# BATT_DISP.net
KiCad netlist of a schematic drawn in EAGLE
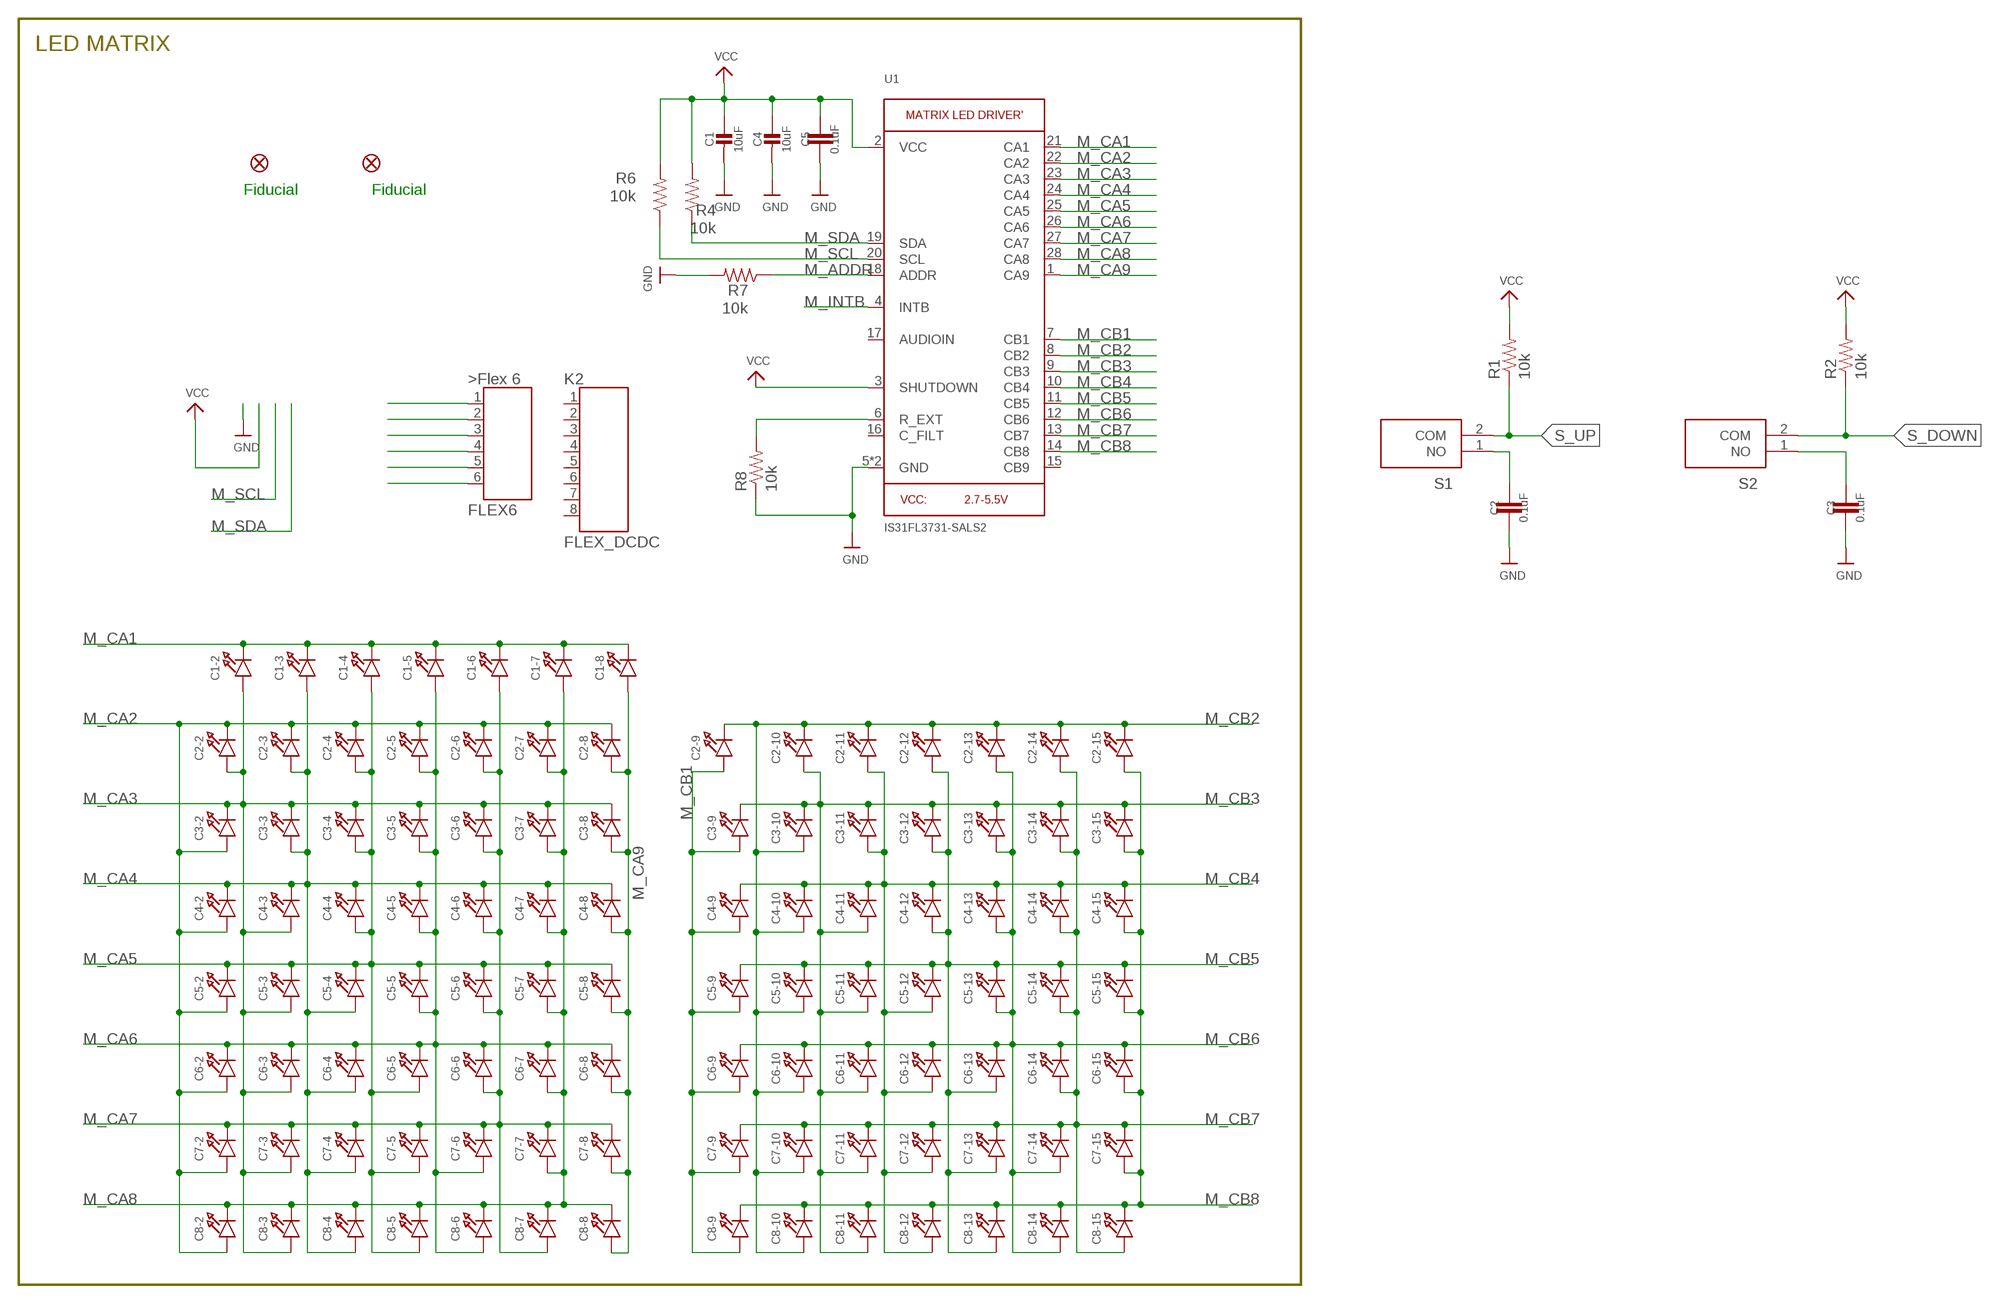
[diagram p0: schematic, sheet 1]

(export (version "E")
  (design (tool "Eeschema 10.0.6"))
  (components
    (comp (ref "C1")
      (value "10uF")
      (footprint "eagle-import:0805-NO")
      (libsource (lib "eagle-import") (part "CAP_CERAMIC0805-NOOUTLINE"))
    )
    (comp (ref "C1-2")
      (value "LED0402_NOOUTLINE")
      (footprint "eagle-import:CHIPLED_0402_NOOUTLINE")
      (libsource (lib "eagle-import") (part "LED0402_NOOUTLINE"))
    )
    (comp (ref "C1-3")
      (value "LED0402_NOOUTLINE")
      (footprint "eagle-import:CHIPLED_0402_NOOUTLINE")
      (libsource (lib "eagle-import") (part "LED0402_NOOUTLINE"))
    )
    (comp (ref "C1-4")
      (value "LED0402_NOOUTLINE")
      (footprint "eagle-import:CHIPLED_0402_NOOUTLINE")
      (libsource (lib "eagle-import") (part "LED0402_NOOUTLINE"))
    )
    (comp (ref "C1-5")
      (value "LED0402_NOOUTLINE")
      (footprint "eagle-import:CHIPLED_0402_NOOUTLINE")
      (libsource (lib "eagle-import") (part "LED0402_NOOUTLINE"))
    )
    (comp (ref "C1-6")
      (value "LED0402_NOOUTLINE")
      (footprint "eagle-import:CHIPLED_0402_NOOUTLINE")
      (libsource (lib "eagle-import") (part "LED0402_NOOUTLINE"))
    )
    (comp (ref "C1-7")
      (value "LED0402_NOOUTLINE")
      (footprint "eagle-import:CHIPLED_0402_NOOUTLINE")
      (libsource (lib "eagle-import") (part "LED0402_NOOUTLINE"))
    )
    (comp (ref "C1-8")
      (value "LED0402_NOOUTLINE")
      (footprint "eagle-import:CHIPLED_0402_NOOUTLINE")
      (libsource (lib "eagle-import") (part "LED0402_NOOUTLINE"))
    )
    (comp (ref "C2")
      (value "0.1uF")
      (footprint "eagle-import:0603")
      (libsource (lib "eagle-import") (part "0.1UF-0603-25V-5%"))
    )
    (comp (ref "C2-2")
      (value "LED0402_NOOUTLINE")
      (footprint "eagle-import:CHIPLED_0402_NOOUTLINE")
      (libsource (lib "eagle-import") (part "LED0402_NOOUTLINE"))
    )
    (comp (ref "C2-3")
      (value "LED0402_NOOUTLINE")
      (footprint "eagle-import:CHIPLED_0402_NOOUTLINE")
      (libsource (lib "eagle-import") (part "LED0402_NOOUTLINE"))
    )
    (comp (ref "C2-4")
      (value "LED0402_NOOUTLINE")
      (footprint "eagle-import:CHIPLED_0402_NOOUTLINE")
      (libsource (lib "eagle-import") (part "LED0402_NOOUTLINE"))
    )
    (comp (ref "C2-5")
      (value "LED0402_NOOUTLINE")
      (footprint "eagle-import:CHIPLED_0402_NOOUTLINE")
      (libsource (lib "eagle-import") (part "LED0402_NOOUTLINE"))
    )
    (comp (ref "C2-6")
      (value "LED0402_NOOUTLINE")
      (footprint "eagle-import:CHIPLED_0402_NOOUTLINE")
      (libsource (lib "eagle-import") (part "LED0402_NOOUTLINE"))
    )
    (comp (ref "C2-7")
      (value "LED0402_NOOUTLINE")
      (footprint "eagle-import:CHIPLED_0402_NOOUTLINE")
      (libsource (lib "eagle-import") (part "LED0402_NOOUTLINE"))
    )
    (comp (ref "C2-8")
      (value "LED0402_NOOUTLINE")
      (footprint "eagle-import:CHIPLED_0402_NOOUTLINE")
      (libsource (lib "eagle-import") (part "LED0402_NOOUTLINE"))
    )
    (comp (ref "C2-9")
      (value "LED0402_NOOUTLINE")
      (footprint "eagle-import:CHIPLED_0402_NOOUTLINE")
      (libsource (lib "eagle-import") (part "LED0402_NOOUTLINE"))
    )
    (comp (ref "C2-10")
      (value "LED0402_NOOUTLINE")
      (footprint "eagle-import:CHIPLED_0402_NOOUTLINE")
      (libsource (lib "eagle-import") (part "LED0402_NOOUTLINE"))
    )
    (comp (ref "C2-11")
      (value "LED0402_NOOUTLINE")
      (footprint "eagle-import:CHIPLED_0402_NOOUTLINE")
      (libsource (lib "eagle-import") (part "LED0402_NOOUTLINE"))
    )
    (comp (ref "C2-12")
      (value "LED0402_NOOUTLINE")
      (footprint "eagle-import:CHIPLED_0402_NOOUTLINE")
      (libsource (lib "eagle-import") (part "LED0402_NOOUTLINE"))
    )
    (comp (ref "C2-13")
      (value "LED0402_NOOUTLINE")
      (footprint "eagle-import:CHIPLED_0402_NOOUTLINE")
      (libsource (lib "eagle-import") (part "LED0402_NOOUTLINE"))
    )
    (comp (ref "C2-14")
      (value "LED0402_NOOUTLINE")
      (footprint "eagle-import:CHIPLED_0402_NOOUTLINE")
      (libsource (lib "eagle-import") (part "LED0402_NOOUTLINE"))
    )
    (comp (ref "C2-15")
      (value "LED0402_NOOUTLINE")
      (footprint "eagle-import:CHIPLED_0402_NOOUTLINE")
      (libsource (lib "eagle-import") (part "LED0402_NOOUTLINE"))
    )
    (comp (ref "C3")
      (value "0.1uF")
      (footprint "eagle-import:0603")
      (libsource (lib "eagle-import") (part "0.1UF-0603-25V-5%"))
    )
    (comp (ref "C3-2")
      (value "LED0402_NOOUTLINE")
      (footprint "eagle-import:CHIPLED_0402_NOOUTLINE")
      (libsource (lib "eagle-import") (part "LED0402_NOOUTLINE"))
    )
    (comp (ref "C3-3")
      (value "LED0402_NOOUTLINE")
      (footprint "eagle-import:CHIPLED_0402_NOOUTLINE")
      (libsource (lib "eagle-import") (part "LED0402_NOOUTLINE"))
    )
    (comp (ref "C3-4")
      (value "LED0402_NOOUTLINE")
      (footprint "eagle-import:CHIPLED_0402_NOOUTLINE")
      (libsource (lib "eagle-import") (part "LED0402_NOOUTLINE"))
    )
    (comp (ref "C3-5")
      (value "LED0402_NOOUTLINE")
      (footprint "eagle-import:CHIPLED_0402_NOOUTLINE")
      (libsource (lib "eagle-import") (part "LED0402_NOOUTLINE"))
    )
    (comp (ref "C3-6")
      (value "LED0402_NOOUTLINE")
      (footprint "eagle-import:CHIPLED_0402_NOOUTLINE")
      (libsource (lib "eagle-import") (part "LED0402_NOOUTLINE"))
    )
    (comp (ref "C3-7")
      (value "LED0402_NOOUTLINE")
      (footprint "eagle-import:CHIPLED_0402_NOOUTLINE")
      (libsource (lib "eagle-import") (part "LED0402_NOOUTLINE"))
    )
    (comp (ref "C3-8")
      (value "LED0402_NOOUTLINE")
      (footprint "eagle-import:CHIPLED_0402_NOOUTLINE")
      (libsource (lib "eagle-import") (part "LED0402_NOOUTLINE"))
    )
    (comp (ref "C3-9")
      (value "LED0402_NOOUTLINE")
      (footprint "eagle-import:CHIPLED_0402_NOOUTLINE")
      (libsource (lib "eagle-import") (part "LED0402_NOOUTLINE"))
    )
    (comp (ref "C3-10")
      (value "LED0402_NOOUTLINE")
      (footprint "eagle-import:CHIPLED_0402_NOOUTLINE")
      (libsource (lib "eagle-import") (part "LED0402_NOOUTLINE"))
    )
    (comp (ref "C3-11")
      (value "LED0402_NOOUTLINE")
      (footprint "eagle-import:CHIPLED_0402_NOOUTLINE")
      (libsource (lib "eagle-import") (part "LED0402_NOOUTLINE"))
    )
    (comp (ref "C3-12")
      (value "LED0402_NOOUTLINE")
      (footprint "eagle-import:CHIPLED_0402_NOOUTLINE")
      (libsource (lib "eagle-import") (part "LED0402_NOOUTLINE"))
    )
    (comp (ref "C3-13")
      (value "LED0402_NOOUTLINE")
      (footprint "eagle-import:CHIPLED_0402_NOOUTLINE")
      (libsource (lib "eagle-import") (part "LED0402_NOOUTLINE"))
    )
    (comp (ref "C3-14")
      (value "LED0402_NOOUTLINE")
      (footprint "eagle-import:CHIPLED_0402_NOOUTLINE")
      (libsource (lib "eagle-import") (part "LED0402_NOOUTLINE"))
    )
    (comp (ref "C3-15")
      (value "LED0402_NOOUTLINE")
      (footprint "eagle-import:CHIPLED_0402_NOOUTLINE")
      (libsource (lib "eagle-import") (part "LED0402_NOOUTLINE"))
    )
    (comp (ref "C4")
      (value "10uF")
      (footprint "eagle-import:0805-NO")
      (libsource (lib "eagle-import") (part "CAP_CERAMIC0805-NOOUTLINE"))
    )
    (comp (ref "C4-2")
      (value "LED0402_NOOUTLINE")
      (footprint "eagle-import:CHIPLED_0402_NOOUTLINE")
      (libsource (lib "eagle-import") (part "LED0402_NOOUTLINE"))
    )
    (comp (ref "C4-3")
      (value "LED0402_NOOUTLINE")
      (footprint "eagle-import:CHIPLED_0402_NOOUTLINE")
      (libsource (lib "eagle-import") (part "LED0402_NOOUTLINE"))
    )
    (comp (ref "C4-4")
      (value "LED0402_NOOUTLINE")
      (footprint "eagle-import:CHIPLED_0402_NOOUTLINE")
      (libsource (lib "eagle-import") (part "LED0402_NOOUTLINE"))
    )
    (comp (ref "C4-5")
      (value "LED0402_NOOUTLINE")
      (footprint "eagle-import:CHIPLED_0402_NOOUTLINE")
      (libsource (lib "eagle-import") (part "LED0402_NOOUTLINE"))
    )
    (comp (ref "C4-6")
      (value "LED0402_NOOUTLINE")
      (footprint "eagle-import:CHIPLED_0402_NOOUTLINE")
      (libsource (lib "eagle-import") (part "LED0402_NOOUTLINE"))
    )
    (comp (ref "C4-7")
      (value "LED0402_NOOUTLINE")
      (footprint "eagle-import:CHIPLED_0402_NOOUTLINE")
      (libsource (lib "eagle-import") (part "LED0402_NOOUTLINE"))
    )
    (comp (ref "C4-8")
      (value "LED0402_NOOUTLINE")
      (footprint "eagle-import:CHIPLED_0402_NOOUTLINE")
      (libsource (lib "eagle-import") (part "LED0402_NOOUTLINE"))
    )
    (comp (ref "C4-9")
      (value "LED0402_NOOUTLINE")
      (footprint "eagle-import:CHIPLED_0402_NOOUTLINE")
      (libsource (lib "eagle-import") (part "LED0402_NOOUTLINE"))
    )
    (comp (ref "C4-10")
      (value "LED0402_NOOUTLINE")
      (footprint "eagle-import:CHIPLED_0402_NOOUTLINE")
      (libsource (lib "eagle-import") (part "LED0402_NOOUTLINE"))
    )
    (comp (ref "C4-11")
      (value "LED0402_NOOUTLINE")
      (footprint "eagle-import:CHIPLED_0402_NOOUTLINE")
      (libsource (lib "eagle-import") (part "LED0402_NOOUTLINE"))
    )
    (comp (ref "C4-12")
      (value "LED0402_NOOUTLINE")
      (footprint "eagle-import:CHIPLED_0402_NOOUTLINE")
      (libsource (lib "eagle-import") (part "LED0402_NOOUTLINE"))
    )
    (comp (ref "C4-13")
      (value "LED0402_NOOUTLINE")
      (footprint "eagle-import:CHIPLED_0402_NOOUTLINE")
      (libsource (lib "eagle-import") (part "LED0402_NOOUTLINE"))
    )
    (comp (ref "C4-14")
      (value "LED0402_NOOUTLINE")
      (footprint "eagle-import:CHIPLED_0402_NOOUTLINE")
      (libsource (lib "eagle-import") (part "LED0402_NOOUTLINE"))
    )
    (comp (ref "C4-15")
      (value "LED0402_NOOUTLINE")
      (footprint "eagle-import:CHIPLED_0402_NOOUTLINE")
      (libsource (lib "eagle-import") (part "LED0402_NOOUTLINE"))
    )
    (comp (ref "C5")
      (value "0.1uF")
      (footprint "eagle-import:0603")
      (libsource (lib "eagle-import") (part "0.1UF-0603-25V-5%"))
    )
    (comp (ref "C5-2")
      (value "LED0402_NOOUTLINE")
      (footprint "eagle-import:CHIPLED_0402_NOOUTLINE")
      (libsource (lib "eagle-import") (part "LED0402_NOOUTLINE"))
    )
    (comp (ref "C5-3")
      (value "LED0402_NOOUTLINE")
      (footprint "eagle-import:CHIPLED_0402_NOOUTLINE")
      (libsource (lib "eagle-import") (part "LED0402_NOOUTLINE"))
    )
    (comp (ref "C5-4")
      (value "LED0402_NOOUTLINE")
      (footprint "eagle-import:CHIPLED_0402_NOOUTLINE")
      (libsource (lib "eagle-import") (part "LED0402_NOOUTLINE"))
    )
    (comp (ref "C5-5")
      (value "LED0402_NOOUTLINE")
      (footprint "eagle-import:CHIPLED_0402_NOOUTLINE")
      (libsource (lib "eagle-import") (part "LED0402_NOOUTLINE"))
    )
    (comp (ref "C5-6")
      (value "LED0402_NOOUTLINE")
      (footprint "eagle-import:CHIPLED_0402_NOOUTLINE")
      (libsource (lib "eagle-import") (part "LED0402_NOOUTLINE"))
    )
    (comp (ref "C5-7")
      (value "LED0402_NOOUTLINE")
      (footprint "eagle-import:CHIPLED_0402_NOOUTLINE")
      (libsource (lib "eagle-import") (part "LED0402_NOOUTLINE"))
    )
    (comp (ref "C5-8")
      (value "LED0402_NOOUTLINE")
      (footprint "eagle-import:CHIPLED_0402_NOOUTLINE")
      (libsource (lib "eagle-import") (part "LED0402_NOOUTLINE"))
    )
    (comp (ref "C5-9")
      (value "LED0402_NOOUTLINE")
      (footprint "eagle-import:CHIPLED_0402_NOOUTLINE")
      (libsource (lib "eagle-import") (part "LED0402_NOOUTLINE"))
    )
    (comp (ref "C5-10")
      (value "LED0402_NOOUTLINE")
      (footprint "eagle-import:CHIPLED_0402_NOOUTLINE")
      (libsource (lib "eagle-import") (part "LED0402_NOOUTLINE"))
    )
    (comp (ref "C5-11")
      (value "LED0402_NOOUTLINE")
      (footprint "eagle-import:CHIPLED_0402_NOOUTLINE")
      (libsource (lib "eagle-import") (part "LED0402_NOOUTLINE"))
    )
    (comp (ref "C5-12")
      (value "LED0402_NOOUTLINE")
      (footprint "eagle-import:CHIPLED_0402_NOOUTLINE")
      (libsource (lib "eagle-import") (part "LED0402_NOOUTLINE"))
    )
    (comp (ref "C5-13")
      (value "LED0402_NOOUTLINE")
      (footprint "eagle-import:CHIPLED_0402_NOOUTLINE")
      (libsource (lib "eagle-import") (part "LED0402_NOOUTLINE"))
    )
    (comp (ref "C5-14")
      (value "LED0402_NOOUTLINE")
      (footprint "eagle-import:CHIPLED_0402_NOOUTLINE")
      (libsource (lib "eagle-import") (part "LED0402_NOOUTLINE"))
    )
    (comp (ref "C5-15")
      (value "LED0402_NOOUTLINE")
      (footprint "eagle-import:CHIPLED_0402_NOOUTLINE")
      (libsource (lib "eagle-import") (part "LED0402_NOOUTLINE"))
    )
    (comp (ref "C6-2")
      (value "LED0402_NOOUTLINE")
      (footprint "eagle-import:CHIPLED_0402_NOOUTLINE")
      (libsource (lib "eagle-import") (part "LED0402_NOOUTLINE"))
    )
    (comp (ref "C6-3")
      (value "LED0402_NOOUTLINE")
      (footprint "eagle-import:CHIPLED_0402_NOOUTLINE")
      (libsource (lib "eagle-import") (part "LED0402_NOOUTLINE"))
    )
    (comp (ref "C6-4")
      (value "LED0402_NOOUTLINE")
      (footprint "eagle-import:CHIPLED_0402_NOOUTLINE")
      (libsource (lib "eagle-import") (part "LED0402_NOOUTLINE"))
    )
    (comp (ref "C6-5")
      (value "LED0402_NOOUTLINE")
      (footprint "eagle-import:CHIPLED_0402_NOOUTLINE")
      (libsource (lib "eagle-import") (part "LED0402_NOOUTLINE"))
    )
    (comp (ref "C6-6")
      (value "LED0402_NOOUTLINE")
      (footprint "eagle-import:CHIPLED_0402_NOOUTLINE")
      (libsource (lib "eagle-import") (part "LED0402_NOOUTLINE"))
    )
    (comp (ref "C6-7")
      (value "LED0402_NOOUTLINE")
      (footprint "eagle-import:CHIPLED_0402_NOOUTLINE")
      (libsource (lib "eagle-import") (part "LED0402_NOOUTLINE"))
    )
    (comp (ref "C6-8")
      (value "LED0402_NOOUTLINE")
      (footprint "eagle-import:CHIPLED_0402_NOOUTLINE")
      (libsource (lib "eagle-import") (part "LED0402_NOOUTLINE"))
    )
    (comp (ref "C6-9")
      (value "LED0402_NOOUTLINE")
      (footprint "eagle-import:CHIPLED_0402_NOOUTLINE")
      (libsource (lib "eagle-import") (part "LED0402_NOOUTLINE"))
    )
    (comp (ref "C6-10")
      (value "LED0402_NOOUTLINE")
      (footprint "eagle-import:CHIPLED_0402_NOOUTLINE")
      (libsource (lib "eagle-import") (part "LED0402_NOOUTLINE"))
    )
    (comp (ref "C6-11")
      (value "LED0402_NOOUTLINE")
      (footprint "eagle-import:CHIPLED_0402_NOOUTLINE")
      (libsource (lib "eagle-import") (part "LED0402_NOOUTLINE"))
    )
    (comp (ref "C6-12")
      (value "LED0402_NOOUTLINE")
      (footprint "eagle-import:CHIPLED_0402_NOOUTLINE")
      (libsource (lib "eagle-import") (part "LED0402_NOOUTLINE"))
    )
    (comp (ref "C6-13")
      (value "LED0402_NOOUTLINE")
      (footprint "eagle-import:CHIPLED_0402_NOOUTLINE")
      (libsource (lib "eagle-import") (part "LED0402_NOOUTLINE"))
    )
    (comp (ref "C6-14")
      (value "LED0402_NOOUTLINE")
      (footprint "eagle-import:CHIPLED_0402_NOOUTLINE")
      (libsource (lib "eagle-import") (part "LED0402_NOOUTLINE"))
    )
    (comp (ref "C6-15")
      (value "LED0402_NOOUTLINE")
      (footprint "eagle-import:CHIPLED_0402_NOOUTLINE")
      (libsource (lib "eagle-import") (part "LED0402_NOOUTLINE"))
    )
    (comp (ref "C7-2")
      (value "LED0402_NOOUTLINE")
      (footprint "eagle-import:CHIPLED_0402_NOOUTLINE")
      (libsource (lib "eagle-import") (part "LED0402_NOOUTLINE"))
    )
    (comp (ref "C7-3")
      (value "LED0402_NOOUTLINE")
      (footprint "eagle-import:CHIPLED_0402_NOOUTLINE")
      (libsource (lib "eagle-import") (part "LED0402_NOOUTLINE"))
    )
    (comp (ref "C7-4")
      (value "LED0402_NOOUTLINE")
      (footprint "eagle-import:CHIPLED_0402_NOOUTLINE")
      (libsource (lib "eagle-import") (part "LED0402_NOOUTLINE"))
    )
    (comp (ref "C7-5")
      (value "LED0402_NOOUTLINE")
      (footprint "eagle-import:CHIPLED_0402_NOOUTLINE")
      (libsource (lib "eagle-import") (part "LED0402_NOOUTLINE"))
    )
    (comp (ref "C7-6")
      (value "LED0402_NOOUTLINE")
      (footprint "eagle-import:CHIPLED_0402_NOOUTLINE")
      (libsource (lib "eagle-import") (part "LED0402_NOOUTLINE"))
    )
    (comp (ref "C7-7")
      (value "LED0402_NOOUTLINE")
      (footprint "eagle-import:CHIPLED_0402_NOOUTLINE")
      (libsource (lib "eagle-import") (part "LED0402_NOOUTLINE"))
    )
    (comp (ref "C7-8")
      (value "LED0402_NOOUTLINE")
      (footprint "eagle-import:CHIPLED_0402_NOOUTLINE")
      (libsource (lib "eagle-import") (part "LED0402_NOOUTLINE"))
    )
    (comp (ref "C7-9")
      (value "LED0402_NOOUTLINE")
      (footprint "eagle-import:CHIPLED_0402_NOOUTLINE")
      (libsource (lib "eagle-import") (part "LED0402_NOOUTLINE"))
    )
    (comp (ref "C7-10")
      (value "LED0402_NOOUTLINE")
      (footprint "eagle-import:CHIPLED_0402_NOOUTLINE")
      (libsource (lib "eagle-import") (part "LED0402_NOOUTLINE"))
    )
    (comp (ref "C7-11")
      (value "LED0402_NOOUTLINE")
      (footprint "eagle-import:CHIPLED_0402_NOOUTLINE")
      (libsource (lib "eagle-import") (part "LED0402_NOOUTLINE"))
    )
    (comp (ref "C7-12")
      (value "LED0402_NOOUTLINE")
      (footprint "eagle-import:CHIPLED_0402_NOOUTLINE")
      (libsource (lib "eagle-import") (part "LED0402_NOOUTLINE"))
    )
    (comp (ref "C7-13")
      (value "LED0402_NOOUTLINE")
      (footprint "eagle-import:CHIPLED_0402_NOOUTLINE")
      (libsource (lib "eagle-import") (part "LED0402_NOOUTLINE"))
    )
    (comp (ref "C7-14")
      (value "LED0402_NOOUTLINE")
      (footprint "eagle-import:CHIPLED_0402_NOOUTLINE")
      (libsource (lib "eagle-import") (part "LED0402_NOOUTLINE"))
    )
    (comp (ref "C7-15")
      (value "LED0402_NOOUTLINE")
      (footprint "eagle-import:CHIPLED_0402_NOOUTLINE")
      (libsource (lib "eagle-import") (part "LED0402_NOOUTLINE"))
    )
    (comp (ref "C8-2")
      (value "LED0402_NOOUTLINE")
      (footprint "eagle-import:CHIPLED_0402_NOOUTLINE")
      (libsource (lib "eagle-import") (part "LED0402_NOOUTLINE"))
    )
    (comp (ref "C8-3")
      (value "LED0402_NOOUTLINE")
      (footprint "eagle-import:CHIPLED_0402_NOOUTLINE")
      (libsource (lib "eagle-import") (part "LED0402_NOOUTLINE"))
    )
    (comp (ref "C8-4")
      (value "LED0402_NOOUTLINE")
      (footprint "eagle-import:CHIPLED_0402_NOOUTLINE")
      (libsource (lib "eagle-import") (part "LED0402_NOOUTLINE"))
    )
    (comp (ref "C8-5")
      (value "LED0402_NOOUTLINE")
      (footprint "eagle-import:CHIPLED_0402_NOOUTLINE")
      (libsource (lib "eagle-import") (part "LED0402_NOOUTLINE"))
    )
    (comp (ref "C8-6")
      (value "LED0402_NOOUTLINE")
      (footprint "eagle-import:CHIPLED_0402_NOOUTLINE")
      (libsource (lib "eagle-import") (part "LED0402_NOOUTLINE"))
    )
    (comp (ref "C8-7")
      (value "LED0402_NOOUTLINE")
      (footprint "eagle-import:CHIPLED_0402_NOOUTLINE")
      (libsource (lib "eagle-import") (part "LED0402_NOOUTLINE"))
    )
    (comp (ref "C8-8")
      (value "LED0402_NOOUTLINE")
      (footprint "eagle-import:CHIPLED_0402_NOOUTLINE")
      (libsource (lib "eagle-import") (part "LED0402_NOOUTLINE"))
    )
    (comp (ref "C8-9")
      (value "LED0402_NOOUTLINE")
      (footprint "eagle-import:CHIPLED_0402_NOOUTLINE")
      (libsource (lib "eagle-import") (part "LED0402_NOOUTLINE"))
    )
    (comp (ref "C8-10")
      (value "LED0402_NOOUTLINE")
      (footprint "eagle-import:CHIPLED_0402_NOOUTLINE")
      (libsource (lib "eagle-import") (part "LED0402_NOOUTLINE"))
    )
    (comp (ref "C8-11")
      (value "LED0402_NOOUTLINE")
      (footprint "eagle-import:CHIPLED_0402_NOOUTLINE")
      (libsource (lib "eagle-import") (part "LED0402_NOOUTLINE"))
    )
    (comp (ref "C8-12")
      (value "LED0402_NOOUTLINE")
      (footprint "eagle-import:CHIPLED_0402_NOOUTLINE")
      (libsource (lib "eagle-import") (part "LED0402_NOOUTLINE"))
    )
    (comp (ref "C8-13")
      (value "LED0402_NOOUTLINE")
      (footprint "eagle-import:CHIPLED_0402_NOOUTLINE")
      (libsource (lib "eagle-import") (part "LED0402_NOOUTLINE"))
    )
    (comp (ref "C8-14")
      (value "LED0402_NOOUTLINE")
      (footprint "eagle-import:CHIPLED_0402_NOOUTLINE")
      (libsource (lib "eagle-import") (part "LED0402_NOOUTLINE"))
    )
    (comp (ref "C8-15")
      (value "LED0402_NOOUTLINE")
      (footprint "eagle-import:CHIPLED_0402_NOOUTLINE")
      (libsource (lib "eagle-import") (part "LED0402_NOOUTLINE"))
    )
    (comp (ref "FD1")
      (value "FIDUCIALUFIDUCIAL")
      (footprint "eagle-import:FIDUCIAL-MICRO")
      (libsource (lib "eagle-import") (part "FIDUCIALUFIDUCIAL"))
    )
    (comp (ref "FD3")
      (value "FIDUCIAL\"\"")
      (footprint "eagle-import:FIDUCIAL_1MM")
      (libsource (lib "eagle-import") (part "FIDUCIAL{dblquote}{dblquote}"))
    )
    (comp (ref "K1")
      (value "FLEX6")
      (footprint "eagle-import:FLEX6")
      (libsource (lib "eagle-import") (part "FLEX6"))
    )
    (comp (ref "K2")
      (value "FLEX_DCDC")
      (footprint "eagle-import:FLEX8")
      (libsource (lib "eagle-import") (part "FLEX8"))
    )
    (comp (ref "R1")
      (value "10k")
      (footprint "eagle-import:0402")
      (libsource (lib "eagle-import") (part "RESISTOR0402"))
    )
    (comp (ref "R2")
      (value "10k")
      (footprint "eagle-import:0402")
      (libsource (lib "eagle-import") (part "RESISTOR0402"))
    )
    (comp (ref "R4")
      (value "10k")
      (footprint "eagle-import:0402")
      (libsource (lib "eagle-import") (part "RESISTOR0402"))
    )
    (comp (ref "R6")
      (value "10k")
      (footprint "eagle-import:0402")
      (libsource (lib "eagle-import") (part "RESISTOR0402"))
    )
    (comp (ref "R7")
      (value "10k")
      (footprint "eagle-import:0402")
      (libsource (lib "eagle-import") (part "RESISTOR0402"))
    )
    (comp (ref "R8")
      (value "10k")
      (footprint "eagle-import:0402")
      (libsource (lib "eagle-import") (part "RESISTOR0402"))
    )
    (comp (ref "S1")
      (value "KXT311LHS")
      (footprint "eagle-import:KXT311LHS")
      (fields (field (name "MOUSER_PART_NUMBER") "611-KXT311LHS"))
      (libsource (lib "eagle-import") (part "KXT311LHS"))
    )
    (comp (ref "S2")
      (value "KXT311LHS")
      (footprint "eagle-import:KXT311LHS")
      (fields (field (name "MOUSER_PART_NUMBER") "611-KXT311LHS"))
      (libsource (lib "eagle-import") (part "KXT311LHS"))
    )
    (comp (ref "U1")
      (value "IS31FL3731-SALS2")
      (footprint "eagle-import:QFN28_4MM_0.4MM")
      (libsource (lib "eagle-import") (part "IS31FL3731QFN"))
    )
  )
  (nets
    (net (code "1") (name "/M_ADDR") (class "Default")
      (node (ref "R7") (pin "1") (pinfunction "1_1") (pintype "passive"))
      (node (ref "U1") (pin "18") (pinfunction "ADDR_18") (pintype "bidirectional"))
    )
    (net (code "2") (name "/M_CA1") (class "Default")
      (node (ref "C1-2") (pin "C") (pinfunction "C_C") (pintype "passive"))
      (node (ref "C1-3") (pin "C") (pinfunction "C_C") (pintype "passive"))
      (node (ref "C1-4") (pin "C") (pinfunction "C_C") (pintype "passive"))
      (node (ref "C1-5") (pin "C") (pinfunction "C_C") (pintype "passive"))
      (node (ref "C1-6") (pin "C") (pinfunction "C_C") (pintype "passive"))
      (node (ref "C1-7") (pin "C") (pinfunction "C_C") (pintype "passive"))
      (node (ref "C1-8") (pin "C") (pinfunction "C_C") (pintype "passive"))
      (node (ref "U1") (pin "21") (pinfunction "CA1_21") (pintype "bidirectional"))
    )
    (net (code "3") (name "/M_CA2") (class "Default")
      (node (ref "C2-2") (pin "C") (pinfunction "C_C") (pintype "passive"))
      (node (ref "C2-3") (pin "C") (pinfunction "C_C") (pintype "passive"))
      (node (ref "C2-4") (pin "C") (pinfunction "C_C") (pintype "passive"))
      (node (ref "C2-5") (pin "C") (pinfunction "C_C") (pintype "passive"))
      (node (ref "C2-6") (pin "C") (pinfunction "C_C") (pintype "passive"))
      (node (ref "C2-7") (pin "C") (pinfunction "C_C") (pintype "passive"))
      (node (ref "C2-8") (pin "C") (pinfunction "C_C") (pintype "passive"))
      (node (ref "C3-2") (pin "A") (pinfunction "A_A") (pintype "passive"))
      (node (ref "C4-2") (pin "A") (pinfunction "A_A") (pintype "passive"))
      (node (ref "C5-2") (pin "A") (pinfunction "A_A") (pintype "passive"))
      (node (ref "C6-2") (pin "A") (pinfunction "A_A") (pintype "passive"))
      (node (ref "C7-2") (pin "A") (pinfunction "A_A") (pintype "passive"))
      (node (ref "C8-2") (pin "A") (pinfunction "A_A") (pintype "passive"))
      (node (ref "U1") (pin "22") (pinfunction "CA2_22") (pintype "bidirectional"))
    )
    (net (code "4") (name "/M_CA3") (class "Default")
      (node (ref "C1-2") (pin "A") (pinfunction "A_A") (pintype "passive"))
      (node (ref "C2-2") (pin "A") (pinfunction "A_A") (pintype "passive"))
      (node (ref "C3-2") (pin "C") (pinfunction "C_C") (pintype "passive"))
      (node (ref "C3-3") (pin "C") (pinfunction "C_C") (pintype "passive"))
      (node (ref "C3-4") (pin "C") (pinfunction "C_C") (pintype "passive"))
      (node (ref "C3-5") (pin "C") (pinfunction "C_C") (pintype "passive"))
      (node (ref "C3-6") (pin "C") (pinfunction "C_C") (pintype "passive"))
      (node (ref "C3-7") (pin "C") (pinfunction "C_C") (pintype "passive"))
      (node (ref "C3-8") (pin "C") (pinfunction "C_C") (pintype "passive"))
      (node (ref "C4-3") (pin "A") (pinfunction "A_A") (pintype "passive"))
      (node (ref "C5-3") (pin "A") (pinfunction "A_A") (pintype "passive"))
      (node (ref "C6-3") (pin "A") (pinfunction "A_A") (pintype "passive"))
      (node (ref "C7-3") (pin "A") (pinfunction "A_A") (pintype "passive"))
      (node (ref "C8-3") (pin "A") (pinfunction "A_A") (pintype "passive"))
      (node (ref "U1") (pin "23") (pinfunction "CA3_23") (pintype "bidirectional"))
    )
    (net (code "5") (name "/M_CA4") (class "Default")
      (node (ref "C1-3") (pin "A") (pinfunction "A_A") (pintype "passive"))
      (node (ref "C2-3") (pin "A") (pinfunction "A_A") (pintype "passive"))
      (node (ref "C3-3") (pin "A") (pinfunction "A_A") (pintype "passive"))
      (node (ref "C4-2") (pin "C") (pinfunction "C_C") (pintype "passive"))
      (node (ref "C4-3") (pin "C") (pinfunction "C_C") (pintype "passive"))
      (node (ref "C4-4") (pin "C") (pinfunction "C_C") (pintype "passive"))
      (node (ref "C4-5") (pin "C") (pinfunction "C_C") (pintype "passive"))
      (node (ref "C4-6") (pin "C") (pinfunction "C_C") (pintype "passive"))
      (node (ref "C4-7") (pin "C") (pinfunction "C_C") (pintype "passive"))
      (node (ref "C4-8") (pin "C") (pinfunction "C_C") (pintype "passive"))
      (node (ref "C5-4") (pin "A") (pinfunction "A_A") (pintype "passive"))
      (node (ref "C6-4") (pin "A") (pinfunction "A_A") (pintype "passive"))
      (node (ref "C7-4") (pin "A") (pinfunction "A_A") (pintype "passive"))
      (node (ref "C8-4") (pin "A") (pinfunction "A_A") (pintype "passive"))
      (node (ref "U1") (pin "24") (pinfunction "CA4_24") (pintype "bidirectional"))
    )
    (net (code "6") (name "/M_CA5") (class "Default")
      (node (ref "C1-4") (pin "A") (pinfunction "A_A") (pintype "passive"))
      (node (ref "C2-4") (pin "A") (pinfunction "A_A") (pintype "passive"))
      (node (ref "C3-4") (pin "A") (pinfunction "A_A") (pintype "passive"))
      (node (ref "C4-4") (pin "A") (pinfunction "A_A") (pintype "passive"))
      (node (ref "C5-2") (pin "C") (pinfunction "C_C") (pintype "passive"))
      (node (ref "C5-3") (pin "C") (pinfunction "C_C") (pintype "passive"))
      (node (ref "C5-4") (pin "C") (pinfunction "C_C") (pintype "passive"))
      (node (ref "C5-5") (pin "C") (pinfunction "C_C") (pintype "passive"))
      (node (ref "C5-6") (pin "C") (pinfunction "C_C") (pintype "passive"))
      (node (ref "C5-7") (pin "C") (pinfunction "C_C") (pintype "passive"))
      (node (ref "C5-8") (pin "C") (pinfunction "C_C") (pintype "passive"))
      (node (ref "C6-5") (pin "A") (pinfunction "A_A") (pintype "passive"))
      (node (ref "C7-5") (pin "A") (pinfunction "A_A") (pintype "passive"))
      (node (ref "C8-5") (pin "A") (pinfunction "A_A") (pintype "passive"))
      (node (ref "U1") (pin "25") (pinfunction "CA5_25") (pintype "bidirectional"))
    )
    (net (code "7") (name "/M_CA6") (class "Default")
      (node (ref "C1-5") (pin "A") (pinfunction "A_A") (pintype "passive"))
      (node (ref "C2-5") (pin "A") (pinfunction "A_A") (pintype "passive"))
      (node (ref "C3-5") (pin "A") (pinfunction "A_A") (pintype "passive"))
      (node (ref "C4-5") (pin "A") (pinfunction "A_A") (pintype "passive"))
      (node (ref "C5-5") (pin "A") (pinfunction "A_A") (pintype "passive"))
      (node (ref "C6-2") (pin "C") (pinfunction "C_C") (pintype "passive"))
      (node (ref "C6-3") (pin "C") (pinfunction "C_C") (pintype "passive"))
      (node (ref "C6-4") (pin "C") (pinfunction "C_C") (pintype "passive"))
      (node (ref "C6-5") (pin "C") (pinfunction "C_C") (pintype "passive"))
      (node (ref "C6-6") (pin "C") (pinfunction "C_C") (pintype "passive"))
      (node (ref "C6-7") (pin "C") (pinfunction "C_C") (pintype "passive"))
      (node (ref "C6-8") (pin "C") (pinfunction "C_C") (pintype "passive"))
      (node (ref "C7-6") (pin "A") (pinfunction "A_A") (pintype "passive"))
      (node (ref "C8-6") (pin "A") (pinfunction "A_A") (pintype "passive"))
      (node (ref "U1") (pin "26") (pinfunction "CA6_26") (pintype "bidirectional"))
    )
    (net (code "8") (name "/M_CA7") (class "Default")
      (node (ref "C1-6") (pin "A") (pinfunction "A_A") (pintype "passive"))
      (node (ref "C2-6") (pin "A") (pinfunction "A_A") (pintype "passive"))
      (node (ref "C3-6") (pin "A") (pinfunction "A_A") (pintype "passive"))
      (node (ref "C4-6") (pin "A") (pinfunction "A_A") (pintype "passive"))
      (node (ref "C5-6") (pin "A") (pinfunction "A_A") (pintype "passive"))
      (node (ref "C6-6") (pin "A") (pinfunction "A_A") (pintype "passive"))
      (node (ref "C7-2") (pin "C") (pinfunction "C_C") (pintype "passive"))
      (node (ref "C7-3") (pin "C") (pinfunction "C_C") (pintype "passive"))
      (node (ref "C7-4") (pin "C") (pinfunction "C_C") (pintype "passive"))
      (node (ref "C7-5") (pin "C") (pinfunction "C_C") (pintype "passive"))
      (node (ref "C7-6") (pin "C") (pinfunction "C_C") (pintype "passive"))
      (node (ref "C7-7") (pin "C") (pinfunction "C_C") (pintype "passive"))
      (node (ref "C7-8") (pin "C") (pinfunction "C_C") (pintype "passive"))
      (node (ref "C8-7") (pin "A") (pinfunction "A_A") (pintype "passive"))
      (node (ref "U1") (pin "27") (pinfunction "CA7_27") (pintype "bidirectional"))
    )
    (net (code "9") (name "/M_CA8") (class "Default")
      (node (ref "C1-7") (pin "A") (pinfunction "A_A") (pintype "passive"))
      (node (ref "C2-7") (pin "A") (pinfunction "A_A") (pintype "passive"))
      (node (ref "C3-7") (pin "A") (pinfunction "A_A") (pintype "passive"))
      (node (ref "C4-7") (pin "A") (pinfunction "A_A") (pintype "passive"))
      (node (ref "C5-7") (pin "A") (pinfunction "A_A") (pintype "passive"))
      (node (ref "C6-7") (pin "A") (pinfunction "A_A") (pintype "passive"))
      (node (ref "C7-7") (pin "A") (pinfunction "A_A") (pintype "passive"))
      (node (ref "C8-2") (pin "C") (pinfunction "C_C") (pintype "passive"))
      (node (ref "C8-3") (pin "C") (pinfunction "C_C") (pintype "passive"))
      (node (ref "C8-4") (pin "C") (pinfunction "C_C") (pintype "passive"))
      (node (ref "C8-5") (pin "C") (pinfunction "C_C") (pintype "passive"))
      (node (ref "C8-6") (pin "C") (pinfunction "C_C") (pintype "passive"))
      (node (ref "C8-7") (pin "C") (pinfunction "C_C") (pintype "passive"))
      (node (ref "C8-8") (pin "C") (pinfunction "C_C") (pintype "passive"))
      (node (ref "U1") (pin "28") (pinfunction "CA8_28") (pintype "bidirectional"))
    )
    (net (code "10") (name "/M_CA9") (class "Default")
      (node (ref "C1-8") (pin "A") (pinfunction "A_A") (pintype "passive"))
      (node (ref "C2-8") (pin "A") (pinfunction "A_A") (pintype "passive"))
      (node (ref "C3-8") (pin "A") (pinfunction "A_A") (pintype "passive"))
      (node (ref "C4-8") (pin "A") (pinfunction "A_A") (pintype "passive"))
      (node (ref "C5-8") (pin "A") (pinfunction "A_A") (pintype "passive"))
      (node (ref "C6-8") (pin "A") (pinfunction "A_A") (pintype "passive"))
      (node (ref "C7-8") (pin "A") (pinfunction "A_A") (pintype "passive"))
      (node (ref "C8-8") (pin "A") (pinfunction "A_A") (pintype "passive"))
      (node (ref "U1") (pin "1") (pinfunction "CA9_1") (pintype "bidirectional"))
    )
    (net (code "11") (name "/M_CB1") (class "Default")
      (node (ref "C2-9") (pin "A") (pinfunction "A_A") (pintype "passive"))
      (node (ref "C3-9") (pin "A") (pinfunction "A_A") (pintype "passive"))
      (node (ref "C4-9") (pin "A") (pinfunction "A_A") (pintype "passive"))
      (node (ref "C5-9") (pin "A") (pinfunction "A_A") (pintype "passive"))
      (node (ref "C6-9") (pin "A") (pinfunction "A_A") (pintype "passive"))
      (node (ref "C7-9") (pin "A") (pinfunction "A_A") (pintype "passive"))
      (node (ref "C8-9") (pin "A") (pinfunction "A_A") (pintype "passive"))
      (node (ref "U1") (pin "7") (pinfunction "CB1_7") (pintype "bidirectional"))
    )
    (net (code "12") (name "/M_CB2") (class "Default")
      (node (ref "C2-10") (pin "C") (pinfunction "C_C") (pintype "passive"))
      (node (ref "C2-11") (pin "C") (pinfunction "C_C") (pintype "passive"))
      (node (ref "C2-12") (pin "C") (pinfunction "C_C") (pintype "passive"))
      (node (ref "C2-13") (pin "C") (pinfunction "C_C") (pintype "passive"))
      (node (ref "C2-14") (pin "C") (pinfunction "C_C") (pintype "passive"))
      (node (ref "C2-15") (pin "C") (pinfunction "C_C") (pintype "passive"))
      (node (ref "C2-9") (pin "C") (pinfunction "C_C") (pintype "passive"))
      (node (ref "C3-10") (pin "A") (pinfunction "A_A") (pintype "passive"))
      (node (ref "C4-10") (pin "A") (pinfunction "A_A") (pintype "passive"))
      (node (ref "C5-10") (pin "A") (pinfunction "A_A") (pintype "passive"))
      (node (ref "C6-10") (pin "A") (pinfunction "A_A") (pintype "passive"))
      (node (ref "C7-10") (pin "A") (pinfunction "A_A") (pintype "passive"))
      (node (ref "C8-10") (pin "A") (pinfunction "A_A") (pintype "passive"))
      (node (ref "U1") (pin "8") (pinfunction "CB2_8") (pintype "bidirectional"))
    )
    (net (code "13") (name "/M_CB3") (class "Default")
      (node (ref "C2-10") (pin "A") (pinfunction "A_A") (pintype "passive"))
      (node (ref "C3-10") (pin "C") (pinfunction "C_C") (pintype "passive"))
      (node (ref "C3-11") (pin "C") (pinfunction "C_C") (pintype "passive"))
      (node (ref "C3-12") (pin "C") (pinfunction "C_C") (pintype "passive"))
      (node (ref "C3-13") (pin "C") (pinfunction "C_C") (pintype "passive"))
      (node (ref "C3-14") (pin "C") (pinfunction "C_C") (pintype "passive"))
      (node (ref "C3-15") (pin "C") (pinfunction "C_C") (pintype "passive"))
      (node (ref "C3-9") (pin "C") (pinfunction "C_C") (pintype "passive"))
      (node (ref "C4-11") (pin "A") (pinfunction "A_A") (pintype "passive"))
      (node (ref "C5-11") (pin "A") (pinfunction "A_A") (pintype "passive"))
      (node (ref "C6-11") (pin "A") (pinfunction "A_A") (pintype "passive"))
      (node (ref "C7-11") (pin "A") (pinfunction "A_A") (pintype "passive"))
      (node (ref "C8-11") (pin "A") (pinfunction "A_A") (pintype "passive"))
      (node (ref "U1") (pin "9") (pinfunction "CB3_9") (pintype "bidirectional"))
    )
    (net (code "14") (name "/M_CB4") (class "Default")
      (node (ref "C2-11") (pin "A") (pinfunction "A_A") (pintype "passive"))
      (node (ref "C3-11") (pin "A") (pinfunction "A_A") (pintype "passive"))
      (node (ref "C4-10") (pin "C") (pinfunction "C_C") (pintype "passive"))
      (node (ref "C4-11") (pin "C") (pinfunction "C_C") (pintype "passive"))
      (node (ref "C4-12") (pin "C") (pinfunction "C_C") (pintype "passive"))
      (node (ref "C4-13") (pin "C") (pinfunction "C_C") (pintype "passive"))
      (node (ref "C4-14") (pin "C") (pinfunction "C_C") (pintype "passive"))
      (node (ref "C4-15") (pin "C") (pinfunction "C_C") (pintype "passive"))
      (node (ref "C4-9") (pin "C") (pinfunction "C_C") (pintype "passive"))
      (node (ref "C5-12") (pin "A") (pinfunction "A_A") (pintype "passive"))
      (node (ref "C6-12") (pin "A") (pinfunction "A_A") (pintype "passive"))
      (node (ref "C7-12") (pin "A") (pinfunction "A_A") (pintype "passive"))
      (node (ref "C8-12") (pin "A") (pinfunction "A_A") (pintype "passive"))
      (node (ref "U1") (pin "10") (pinfunction "CB4_10") (pintype "bidirectional"))
    )
    (net (code "15") (name "/M_CB5") (class "Default")
      (node (ref "C2-12") (pin "A") (pinfunction "A_A") (pintype "passive"))
      (node (ref "C3-12") (pin "A") (pinfunction "A_A") (pintype "passive"))
      (node (ref "C4-12") (pin "A") (pinfunction "A_A") (pintype "passive"))
      (node (ref "C5-10") (pin "C") (pinfunction "C_C") (pintype "passive"))
      (node (ref "C5-11") (pin "C") (pinfunction "C_C") (pintype "passive"))
      (node (ref "C5-12") (pin "C") (pinfunction "C_C") (pintype "passive"))
      (node (ref "C5-13") (pin "C") (pinfunction "C_C") (pintype "passive"))
      (node (ref "C5-14") (pin "C") (pinfunction "C_C") (pintype "passive"))
      (node (ref "C5-15") (pin "C") (pinfunction "C_C") (pintype "passive"))
      (node (ref "C5-9") (pin "C") (pinfunction "C_C") (pintype "passive"))
      (node (ref "C6-13") (pin "A") (pinfunction "A_A") (pintype "passive"))
      (node (ref "C7-13") (pin "A") (pinfunction "A_A") (pintype "passive"))
      (node (ref "C8-13") (pin "A") (pinfunction "A_A") (pintype "passive"))
      (node (ref "U1") (pin "11") (pinfunction "CB5_11") (pintype "bidirectional"))
    )
    (net (code "16") (name "/M_CB6") (class "Default")
      (node (ref "C2-13") (pin "A") (pinfunction "A_A") (pintype "passive"))
      (node (ref "C3-13") (pin "A") (pinfunction "A_A") (pintype "passive"))
      (node (ref "C4-13") (pin "A") (pinfunction "A_A") (pintype "passive"))
      (node (ref "C5-13") (pin "A") (pinfunction "A_A") (pintype "passive"))
      (node (ref "C6-10") (pin "C") (pinfunction "C_C") (pintype "passive"))
      (node (ref "C6-11") (pin "C") (pinfunction "C_C") (pintype "passive"))
      (node (ref "C6-12") (pin "C") (pinfunction "C_C") (pintype "passive"))
      (node (ref "C6-13") (pin "C") (pinfunction "C_C") (pintype "passive"))
      (node (ref "C6-14") (pin "C") (pinfunction "C_C") (pintype "passive"))
      (node (ref "C6-15") (pin "C") (pinfunction "C_C") (pintype "passive"))
      (node (ref "C6-9") (pin "C") (pinfunction "C_C") (pintype "passive"))
      (node (ref "C7-14") (pin "A") (pinfunction "A_A") (pintype "passive"))
      (node (ref "C8-14") (pin "A") (pinfunction "A_A") (pintype "passive"))
      (node (ref "U1") (pin "12") (pinfunction "CB6_12") (pintype "bidirectional"))
    )
    (net (code "17") (name "/M_CB7") (class "Default")
      (node (ref "C2-14") (pin "A") (pinfunction "A_A") (pintype "passive"))
      (node (ref "C3-14") (pin "A") (pinfunction "A_A") (pintype "passive"))
      (node (ref "C4-14") (pin "A") (pinfunction "A_A") (pintype "passive"))
      (node (ref "C5-14") (pin "A") (pinfunction "A_A") (pintype "passive"))
      (node (ref "C6-14") (pin "A") (pinfunction "A_A") (pintype "passive"))
      (node (ref "C7-10") (pin "C") (pinfunction "C_C") (pintype "passive"))
      (node (ref "C7-11") (pin "C") (pinfunction "C_C") (pintype "passive"))
      (node (ref "C7-12") (pin "C") (pinfunction "C_C") (pintype "passive"))
      (node (ref "C7-13") (pin "C") (pinfunction "C_C") (pintype "passive"))
      (node (ref "C7-14") (pin "C") (pinfunction "C_C") (pintype "passive"))
      (node (ref "C7-15") (pin "C") (pinfunction "C_C") (pintype "passive"))
      (node (ref "C7-9") (pin "C") (pinfunction "C_C") (pintype "passive"))
      (node (ref "C8-15") (pin "A") (pinfunction "A_A") (pintype "passive"))
      (node (ref "U1") (pin "13") (pinfunction "CB7_13") (pintype "bidirectional"))
    )
    (net (code "18") (name "/M_CB8") (class "Default")
      (node (ref "C2-15") (pin "A") (pinfunction "A_A") (pintype "passive"))
      (node (ref "C3-15") (pin "A") (pinfunction "A_A") (pintype "passive"))
      (node (ref "C4-15") (pin "A") (pinfunction "A_A") (pintype "passive"))
      (node (ref "C5-15") (pin "A") (pinfunction "A_A") (pintype "passive"))
      (node (ref "C6-15") (pin "A") (pinfunction "A_A") (pintype "passive"))
      (node (ref "C7-15") (pin "A") (pinfunction "A_A") (pintype "passive"))
      (node (ref "C8-10") (pin "C") (pinfunction "C_C") (pintype "passive"))
      (node (ref "C8-11") (pin "C") (pinfunction "C_C") (pintype "passive"))
      (node (ref "C8-12") (pin "C") (pinfunction "C_C") (pintype "passive"))
      (node (ref "C8-13") (pin "C") (pinfunction "C_C") (pintype "passive"))
      (node (ref "C8-14") (pin "C") (pinfunction "C_C") (pintype "passive"))
      (node (ref "C8-15") (pin "C") (pinfunction "C_C") (pintype "passive"))
      (node (ref "C8-9") (pin "C") (pinfunction "C_C") (pintype "passive"))
      (node (ref "U1") (pin "14") (pinfunction "CB8_14") (pintype "bidirectional"))
    )
    (net (code "19") (name "/M_INTB") (class "Default")
      (node (ref "U1") (pin "4") (pinfunction "INTB_4") (pintype "output"))
    )
    (net (code "20") (name "/M_SCL") (class "Default")
      (node (ref "R6") (pin "1") (pinfunction "1_1") (pintype "passive"))
      (node (ref "U1") (pin "20") (pinfunction "SCL_20") (pintype "bidirectional"))
    )
    (net (code "21") (name "/M_SDA") (class "Default")
      (node (ref "R4") (pin "1") (pinfunction "1_1") (pintype "passive"))
      (node (ref "U1") (pin "19") (pinfunction "SDA_19") (pintype "bidirectional"))
    )
    (net (code "22") (name "GND") (class "Default")
      (node (ref "C1") (pin "2") (pinfunction "2_2") (pintype "passive"))
      (node (ref "C2") (pin "2") (pinfunction "2_2") (pintype "passive"))
      (node (ref "C3") (pin "2") (pinfunction "2_2") (pintype "passive"))
      (node (ref "C4") (pin "2") (pinfunction "2_2") (pintype "passive"))
      (node (ref "C5") (pin "2") (pinfunction "2_2") (pintype "passive"))
      (node (ref "R7") (pin "2") (pinfunction "2_2") (pintype "passive"))
      (node (ref "R8") (pin "1") (pinfunction "1_1") (pintype "passive"))
      (node (ref "U1") (pin "5") (pinfunction "GND_5") (pintype "power_in"))
      (node (ref "U1") (pin "THERMAL") (pinfunction "GND_THERMAL") (pintype "power_in"))
    )
    (net (code "23") (name "Net-(S1-NO)") (class "Default")
      (node (ref "C2") (pin "1") (pinfunction "1_1") (pintype "passive"))
      (node (ref "S1") (pin "1") (pinfunction "NO_1") (pintype "bidirectional"))
    )
    (net (code "24") (name "Net-(S2-NO)") (class "Default")
      (node (ref "C3") (pin "1") (pinfunction "1_1") (pintype "passive"))
      (node (ref "S2") (pin "1") (pinfunction "NO_1") (pintype "bidirectional"))
    )
    (net (code "25") (name "Net-(U1-R_EXT)") (class "Default")
      (node (ref "R8") (pin "2") (pinfunction "2_2") (pintype "passive"))
      (node (ref "U1") (pin "6") (pinfunction "R_EXT_6") (pintype "bidirectional"))
    )
    (net (code "26") (name "S_DOWN") (class "Default")
      (node (ref "R2") (pin "1") (pinfunction "1_1") (pintype "passive"))
      (node (ref "S2") (pin "2") (pinfunction "COM_2") (pintype "bidirectional"))
    )
    (net (code "27") (name "S_UP") (class "Default")
      (node (ref "R1") (pin "1") (pinfunction "1_1") (pintype "passive"))
      (node (ref "S1") (pin "2") (pinfunction "COM_2") (pintype "bidirectional"))
    )
    (net (code "28") (name "VCC") (class "Default")
      (node (ref "C1") (pin "1") (pinfunction "1_1") (pintype "passive"))
      (node (ref "C4") (pin "1") (pinfunction "1_1") (pintype "passive"))
      (node (ref "C5") (pin "1") (pinfunction "1_1") (pintype "passive"))
      (node (ref "R1") (pin "2") (pinfunction "2_2") (pintype "passive"))
      (node (ref "R2") (pin "2") (pinfunction "2_2") (pintype "passive"))
      (node (ref "R4") (pin "2") (pinfunction "2_2") (pintype "passive"))
      (node (ref "R6") (pin "2") (pinfunction "2_2") (pintype "passive"))
      (node (ref "U1") (pin "2") (pinfunction "VCC_2") (pintype "power_in"))
      (node (ref "U1") (pin "3") (pinfunction "SHUTDOWN_3") (pintype "input"))
    )
    (net (code "29") (name "unconnected-(K1-Pad1)") (class "Default")
      (node (ref "K1") (pin "1") (pinfunction "1_1") (pintype "passive"))
    )
    (net (code "30") (name "unconnected-(K1-Pad2)") (class "Default")
      (node (ref "K1") (pin "2") (pinfunction "2_2") (pintype "passive"))
    )
    (net (code "31") (name "unconnected-(K1-Pad3)") (class "Default")
      (node (ref "K1") (pin "3") (pinfunction "3_3") (pintype "passive"))
    )
    (net (code "32") (name "unconnected-(K1-Pad4)") (class "Default")
      (node (ref "K1") (pin "4") (pinfunction "4_4") (pintype "passive"))
    )
    (net (code "33") (name "unconnected-(K1-Pad5)") (class "Default")
      (node (ref "K1") (pin "5") (pinfunction "5_5") (pintype "passive"))
    )
    (net (code "34") (name "unconnected-(K1-Pad6)") (class "Default")
      (node (ref "K1") (pin "6") (pinfunction "6_6") (pintype "passive"))
    )
    (net (code "35") (name "unconnected-(K2-Pad1)") (class "Default")
      (node (ref "K2") (pin "1") (pinfunction "1_1") (pintype "passive"))
    )
    (net (code "36") (name "unconnected-(K2-Pad2)") (class "Default")
      (node (ref "K2") (pin "2") (pinfunction "2_2") (pintype "passive"))
    )
    (net (code "37") (name "unconnected-(K2-Pad3)") (class "Default")
      (node (ref "K2") (pin "3") (pinfunction "3_3") (pintype "passive"))
    )
    (net (code "38") (name "unconnected-(K2-Pad4)") (class "Default")
      (node (ref "K2") (pin "4") (pinfunction "4_4") (pintype "passive"))
    )
    (net (code "39") (name "unconnected-(K2-Pad5)") (class "Default")
      (node (ref "K2") (pin "5") (pinfunction "5_5") (pintype "passive"))
    )
    (net (code "40") (name "unconnected-(K2-Pad6)") (class "Default")
      (node (ref "K2") (pin "6") (pinfunction "6_6") (pintype "passive"))
    )
    (net (code "41") (name "unconnected-(K2-Pad7)") (class "Default")
      (node (ref "K2") (pin "7") (pinfunction "7_7") (pintype "passive"))
    )
    (net (code "42") (name "unconnected-(K2-Pad8)") (class "Default")
      (node (ref "K2") (pin "8") (pinfunction "8_8") (pintype "passive"))
    )
    (net (code "43") (name "unconnected-(U1-AUDIOIN-Pad17)") (class "Default")
      (node (ref "U1") (pin "17") (pinfunction "AUDIOIN_17") (pintype "input"))
    )
    (net (code "44") (name "unconnected-(U1-CB9-Pad15)") (class "Default")
      (node (ref "U1") (pin "15") (pinfunction "CB9_15") (pintype "bidirectional"))
    )
    (net (code "45") (name "unconnected-(U1-C_FILT-Pad16)") (class "Default")
      (node (ref "U1") (pin "16") (pinfunction "C_FILT_16") (pintype "bidirectional"))
    )
  )
)
